# accel_RevA.net
KiCad netlist of a schematic drawn in EAGLE
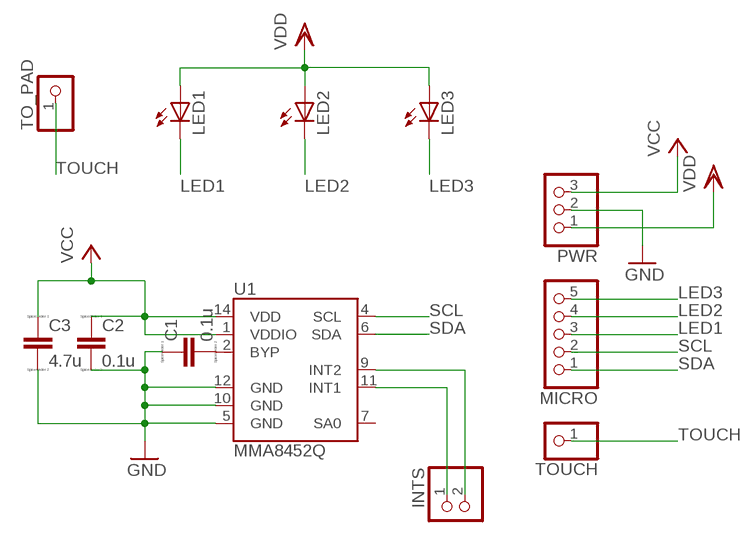
[diagram p0: schematic, sheet 1]

(export (version "E")
  (design (tool "Eeschema 10.0.6"))
  (components
    (comp (ref "C1")
      (value "0.1u")
      (footprint "eagle-import:C0603")
      (libsource (lib "eagle-import") (part "CC0603"))
    )
    (comp (ref "C2")
      (value "0.1u")
      (footprint "eagle-import:C0603")
      (libsource (lib "eagle-import") (part "CC0603"))
    )
    (comp (ref "C3")
      (value "4.7u")
      (footprint "eagle-import:C0603")
      (libsource (lib "eagle-import") (part "CC0603"))
    )
    (comp (ref "INTS")
      (value "PINHD-1X2")
      (footprint "eagle-import:1X02")
      (libsource (lib "eagle-import") (part "PINHD-1X2"))
    )
    (comp (ref "LED1")
      (value "LEDP-LCC-4")
      (footprint "eagle-import:P-LCC-4")
      (libsource (lib "eagle-import") (part "LEDP-LCC-4"))
    )
    (comp (ref "LED2")
      (value "LEDP-LCC-4")
      (footprint "eagle-import:P-LCC-4")
      (libsource (lib "eagle-import") (part "LEDP-LCC-4"))
    )
    (comp (ref "LED3")
      (value "LEDP-LCC-4")
      (footprint "eagle-import:P-LCC-4")
      (libsource (lib "eagle-import") (part "LEDP-LCC-4"))
    )
    (comp (ref "MICRO")
      (value "PINHD-1X5")
      (footprint "eagle-import:1X05")
      (libsource (lib "eagle-import") (part "PINHD-1X5"))
    )
    (comp (ref "PWR")
      (value "PINHD-1X3")
      (footprint "eagle-import:1X03")
      (libsource (lib "eagle-import") (part "PINHD-1X3"))
    )
    (comp (ref "TOUCH")
      (value "PINHD-1X1")
      (footprint "eagle-import:1X01")
      (libsource (lib "eagle-import") (part "PINHD-1X1"))
    )
    (comp (ref "TO_PAD")
      (value "PINHD-1X1")
      (footprint "eagle-import:1X01")
      (libsource (lib "eagle-import") (part "PINHD-1X1"))
    )
    (comp (ref "U1")
      (value "MMA8452Q")
      (footprint "eagle-import:QFN-16_0.5MM")
      (libsource (lib "eagle-import") (part "MMA8452Q"))
    )
  )
  (nets
    (net (code "1") (name "/LED1") (class "Default")
      (node (ref "LED1") (pin "C@4") (pinfunction "C_C@4") (pintype "passive"))
      (node (ref "MICRO") (pin "3") (pinfunction "3_3") (pintype "passive"))
    )
    (net (code "2") (name "/LED2") (class "Default")
      (node (ref "LED2") (pin "C@4") (pinfunction "C_C@4") (pintype "passive"))
      (node (ref "MICRO") (pin "4") (pinfunction "4_4") (pintype "passive"))
    )
    (net (code "3") (name "/LED3") (class "Default")
      (node (ref "LED3") (pin "C@4") (pinfunction "C_C@4") (pintype "passive"))
      (node (ref "MICRO") (pin "5") (pinfunction "5_5") (pintype "passive"))
    )
    (net (code "4") (name "/SCL") (class "Default")
      (node (ref "MICRO") (pin "2") (pinfunction "2_2") (pintype "passive"))
      (node (ref "U1") (pin "4") (pinfunction "SCL_4") (pintype "bidirectional"))
    )
    (net (code "5") (name "/SDA") (class "Default")
      (node (ref "MICRO") (pin "1") (pinfunction "1_1") (pintype "passive"))
      (node (ref "U1") (pin "6") (pinfunction "SDA_6") (pintype "bidirectional"))
    )
    (net (code "6") (name "/TOUCH") (class "Default")
      (node (ref "TOUCH") (pin "1") (pinfunction "1_1") (pintype "passive"))
      (node (ref "TO_PAD") (pin "1") (pinfunction "1_1") (pintype "passive"))
    )
    (net (code "7") (name "GND") (class "Default")
      (node (ref "C1") (pin "1") (pinfunction "1_1") (pintype "passive"))
      (node (ref "C2") (pin "2") (pinfunction "2_2") (pintype "passive"))
      (node (ref "C3") (pin "2") (pinfunction "2_2") (pintype "passive"))
      (node (ref "PWR") (pin "2") (pinfunction "2_2") (pintype "passive"))
      (node (ref "U1") (pin "10") (pinfunction "GND_10") (pintype "bidirectional"))
      (node (ref "U1") (pin "12") (pinfunction "GND_12") (pintype "bidirectional"))
      (node (ref "U1") (pin "5") (pinfunction "GND_5") (pintype "bidirectional"))
    )
    (net (code "8") (name "Net-(U1-BYP)") (class "Default")
      (node (ref "C1") (pin "2") (pinfunction "2_2") (pintype "passive"))
      (node (ref "U1") (pin "2") (pinfunction "BYP_2") (pintype "bidirectional"))
    )
    (net (code "9") (name "Net-(U1-INT1)") (class "Default")
      (node (ref "INTS") (pin "1") (pinfunction "1_1") (pintype "passive"))
      (node (ref "U1") (pin "11") (pinfunction "INT1_11") (pintype "bidirectional"))
    )
    (net (code "10") (name "Net-(U1-INT2)") (class "Default")
      (node (ref "INTS") (pin "2") (pinfunction "2_2") (pintype "passive"))
      (node (ref "U1") (pin "9") (pinfunction "INT2_9") (pintype "bidirectional"))
    )
    (net (code "11") (name "VCC") (class "Default")
      (node (ref "C2") (pin "1") (pinfunction "1_1") (pintype "passive"))
      (node (ref "C3") (pin "1") (pinfunction "1_1") (pintype "passive"))
      (node (ref "PWR") (pin "3") (pinfunction "3_3") (pintype "passive"))
      (node (ref "U1") (pin "1") (pinfunction "VDDIO_1") (pintype "bidirectional"))
      (node (ref "U1") (pin "14") (pinfunction "VDD_14") (pintype "bidirectional"))
    )
    (net (code "12") (name "VDD") (class "Default")
      (node (ref "LED1") (pin "A") (pinfunction "A_A") (pintype "passive"))
      (node (ref "LED2") (pin "A") (pinfunction "A_A") (pintype "passive"))
      (node (ref "LED3") (pin "A") (pinfunction "A_A") (pintype "passive"))
      (node (ref "PWR") (pin "1") (pinfunction "1_1") (pintype "passive"))
    )
    (net (code "13") (name "unconnected-(U1-SA0-Pad7)") (class "Default")
      (node (ref "U1") (pin "7") (pinfunction "SA0_7") (pintype "bidirectional"))
    )
  )
)
